# OPT.net
KiCad netlist of a schematic drawn in Altium Designer
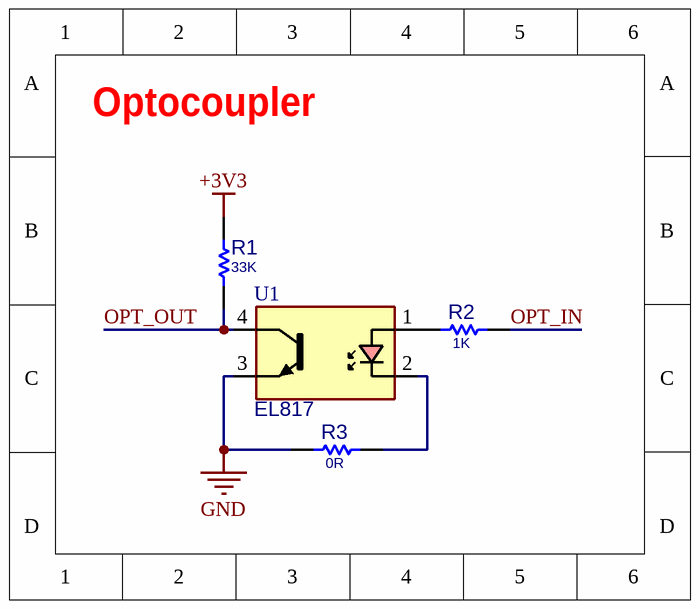
[diagram p0: OPT.SchDoc]

(export (version "E")
  (design (tool "Eeschema 10.0.6"))
  (components
    (comp (ref "R1")
      (value "33K")
      (footprint "R0603")
      (description "RES, SMD")
      (fields (field (name "MANF_P#") "RK73H1ETTP4701F") (field (name "MANF") "KOA SPEER"))
      (libsource (lib "PW Components 97_481") (part "RES_SMD"))
    )
    (comp (ref "R2")
      (value "1K")
      (footprint "R0603")
      (description "RES, SMD")
      (fields (field (name "MANF_P#") "RK73H1ETTP4701F") (field (name "MANF") "KOA SPEER"))
      (libsource (lib "PW Components 97_481") (part "RES_SMD"))
    )
    (comp (ref "R3")
      (value "0R")
      (footprint "R0603")
      (description "RES, SMD")
      (fields (field (name "MANF_P#") "RK73H1ETTP4701F") (field (name "MANF") "KOA SPEER"))
      (libsource (lib "PW Components 97_481") (part "RES_SMD"))
    )
    (comp (ref "U1")
      (value "EL817")
      (footprint "DIP_4SMD")
      (description "OPTOCOUPLER, TRANSISTOR, 4PIN")
      (libsource (lib "PW Components 97_481") (part "OPTC_TR4P_EL817_SMD"))
    )
  )
  (nets
    (net (code "1") (name "+3V3") (class "Default")
      (node (ref "R1") (pin "1") (pinfunction "1_1") (pintype "passive"))
    )
    (net (code "2") (name "/OPT_IN") (class "Default")
      (node (ref "R2") (pin "1") (pinfunction "1_1") (pintype "passive"))
    )
    (net (code "3") (name "/OPT_OUT") (class "Default")
      (node (ref "R1") (pin "2") (pinfunction "2_2") (pintype "passive"))
      (node (ref "U1") (pin "4") (pinfunction "C_4") (pintype "passive"))
    )
    (net (code "4") (name "GND") (class "Default")
      (node (ref "R3") (pin "2") (pinfunction "2_2") (pintype "passive"))
      (node (ref "U1") (pin "3") (pinfunction "E_3") (pintype "passive"))
    )
    (net (code "5") (name "Net-(U1-A)") (class "Default")
      (node (ref "R2") (pin "2") (pinfunction "2_2") (pintype "passive"))
      (node (ref "U1") (pin "1") (pinfunction "A_1") (pintype "passive"))
    )
    (net (code "6") (name "Net-(U1-K)") (class "Default")
      (node (ref "R3") (pin "1") (pinfunction "1_1") (pintype "passive"))
      (node (ref "U1") (pin "2") (pinfunction "K_2") (pintype "passive"))
    )
  )
)
